# Adafruit_PowerBoost_Shield.net
KiCad netlist of a schematic drawn in EAGLE
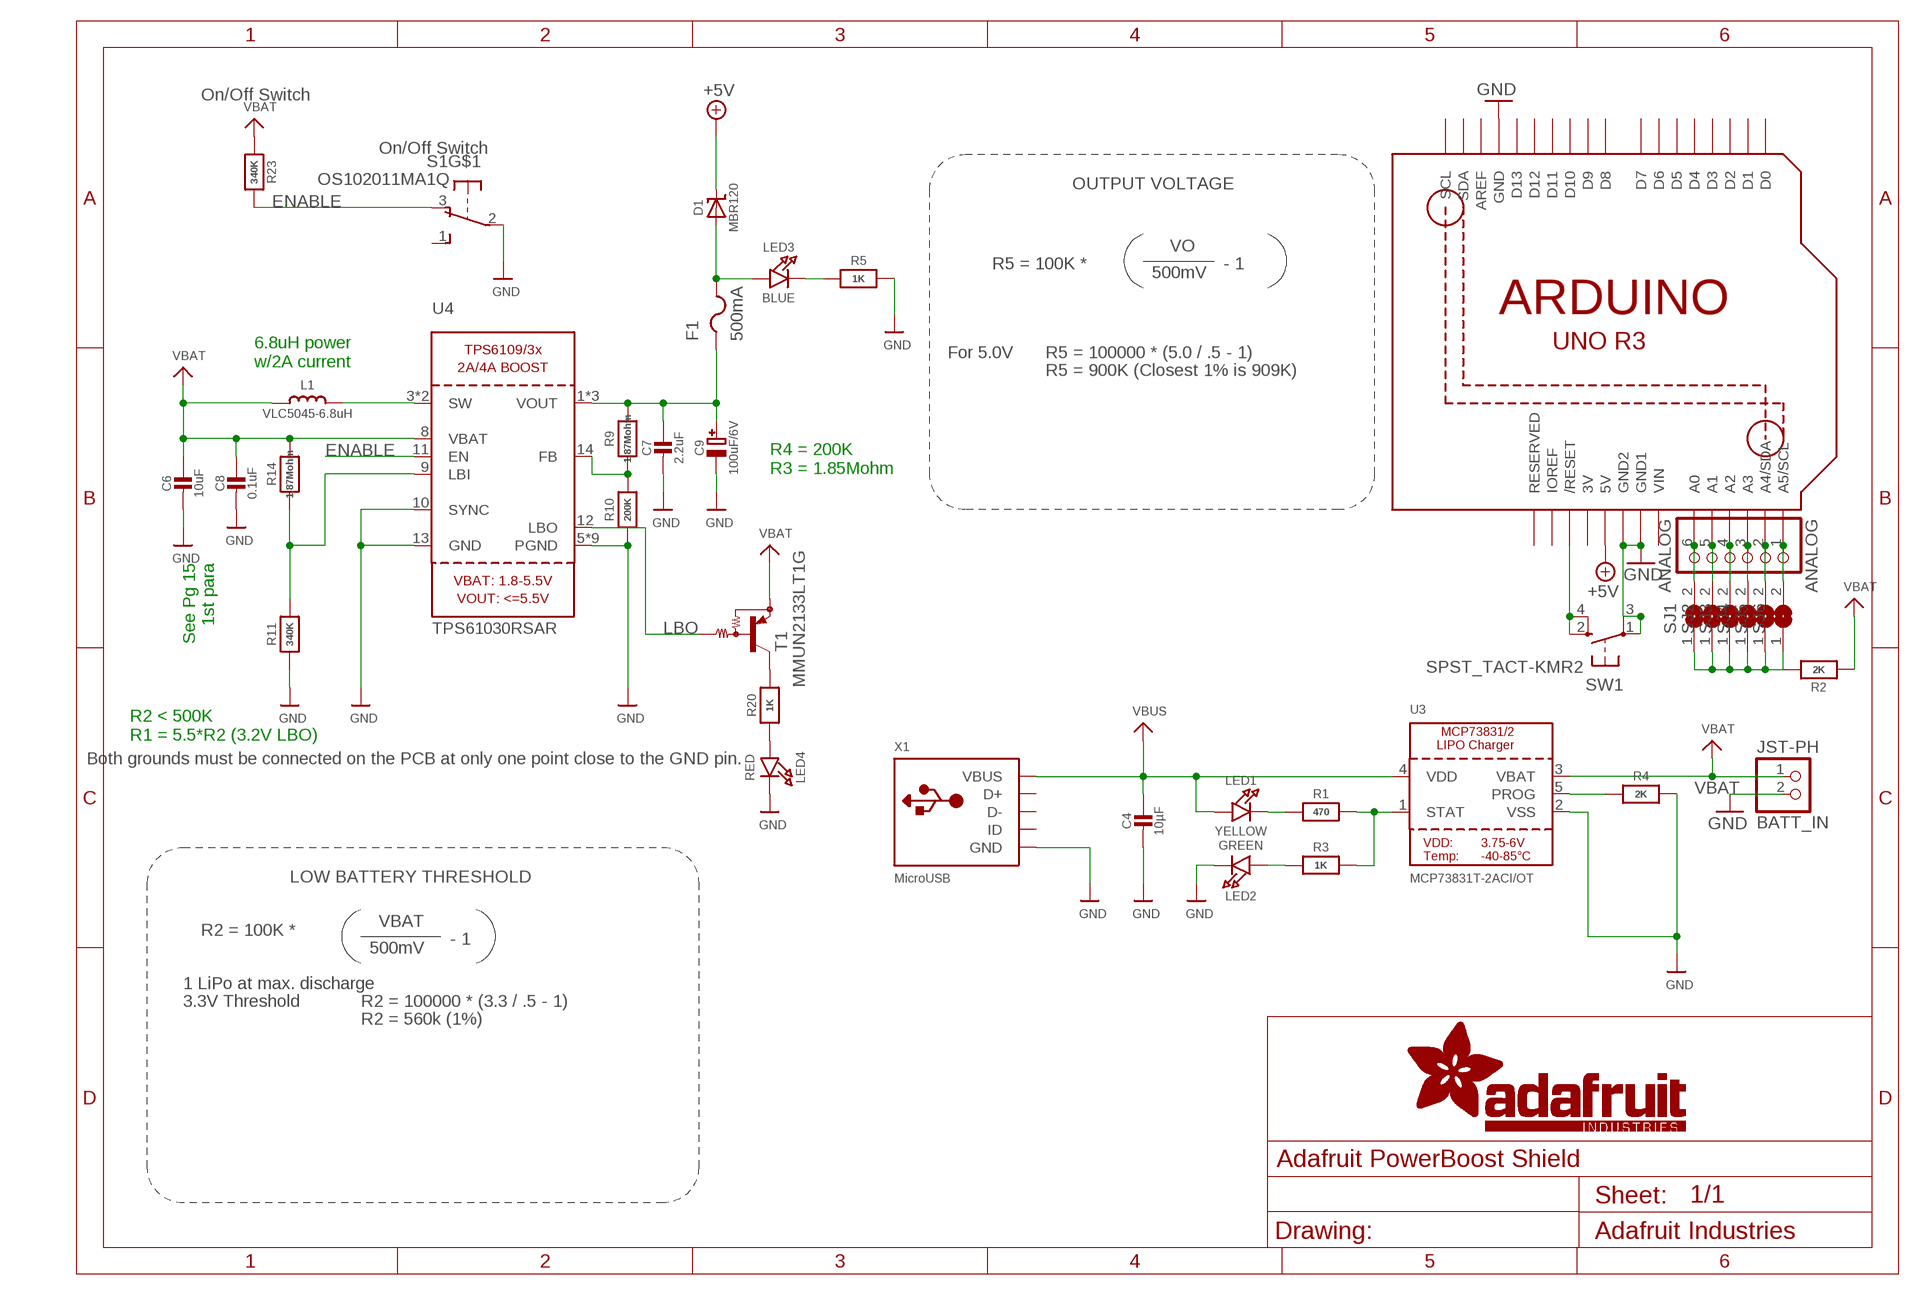
[diagram p0: schematic, sheet 1]

(export (version "E")
  (design (tool "Eeschema 10.0.6"))
  (components
    (comp (ref "ANALOG")
      (value "ANALOG")
      (footprint "eagle-import:1X06")
      (libsource (lib "eagle-import") (part "PINHD-1X6"))
    )
    (comp (ref "BATT_IN")
      (value "JST-PH")
      (footprint "eagle-import:JST-PH-2-SMT")
      (libsource (lib "eagle-import") (part "JST_2PIN-SMT"))
    )
    (comp (ref "C4")
      (value "10µF")
      (footprint "eagle-import:0805-NO")
      (libsource (lib "eagle-import") (part "CAP_CERAMIC0805-NOOUTLINE"))
    )
    (comp (ref "C6")
      (value "10uF")
      (footprint "eagle-import:0805-NO")
      (libsource (lib "eagle-import") (part "CAP_CERAMIC0805-NOOUTLINE"))
    )
    (comp (ref "C7")
      (value "2.2uF")
      (footprint "eagle-import:0805-NO")
      (libsource (lib "eagle-import") (part "CAP_CERAMIC0805-NOOUTLINE"))
    )
    (comp (ref "C8")
      (value "0.1uF")
      (footprint "eagle-import:0805-NO")
      (libsource (lib "eagle-import") (part "CAP_CERAMIC0805-NOOUTLINE"))
    )
    (comp (ref "C9")
      (value "100uF/6V")
      (footprint "eagle-import:EIA3528-21_B-R")
      (libsource (lib "eagle-import") (part "CAP_TANTALUMB/3528_REFLOW"))
    )
    (comp (ref "D1")
      (value "MBR120")
      (footprint "eagle-import:SOD-123")
      (libsource (lib "eagle-import") (part "DIODE-SCHOTTKYSOD-123"))
    )
    (comp (ref "F1")
      (value "500mA")
      (footprint "eagle-import:R1206")
      (libsource (lib "eagle-import") (part "PTCFUSE-1206"))
    )
    (comp (ref "L1")
      (value "VLC5045-6.8uH")
      (footprint "eagle-import:INDUCTOR_5X5MM_TDK_VLC5045")
      (libsource (lib "eagle-import") (part "INDUCTORTDK_VLC5045"))
    )
    (comp (ref "LED1")
      (value "YELLOW")
      (footprint "eagle-import:CHIPLED_0805_NOOUTLINE")
      (libsource (lib "eagle-import") (part "LED0805_NOOUTLINE"))
    )
    (comp (ref "LED2")
      (value "GREEN")
      (footprint "eagle-import:CHIPLED_0805_NOOUTLINE")
      (libsource (lib "eagle-import") (part "LED0805_NOOUTLINE"))
    )
    (comp (ref "LED3")
      (value "BLUE")
      (footprint "eagle-import:CHIPLED_0805_NOOUTLINE")
      (libsource (lib "eagle-import") (part "LED0805_NOOUTLINE"))
    )
    (comp (ref "LED4")
      (value "RED")
      (footprint "eagle-import:CHIPLED_0805_NOOUTLINE")
      (libsource (lib "eagle-import") (part "LED0805_NOOUTLINE"))
    )
    (comp (ref "R1")
      (value "470")
      (footprint "eagle-import:0805-NO")
      (libsource (lib "eagle-import") (part "RESISTOR0805_NOOUTLINE"))
    )
    (comp (ref "R2")
      (value "2K")
      (footprint "eagle-import:0805-NO")
      (libsource (lib "eagle-import") (part "RESISTOR0805_NOOUTLINE"))
    )
    (comp (ref "R3")
      (value "1K")
      (footprint "eagle-import:0805-NO")
      (libsource (lib "eagle-import") (part "RESISTOR0805_NOOUTLINE"))
    )
    (comp (ref "R4")
      (value "2K")
      (footprint "eagle-import:0805-NO")
      (libsource (lib "eagle-import") (part "RESISTOR0805_NOOUTLINE"))
    )
    (comp (ref "R5")
      (value "1K")
      (footprint "eagle-import:0805-NO")
      (libsource (lib "eagle-import") (part "RESISTOR0805_NOOUTLINE"))
    )
    (comp (ref "R9")
      (value "1.87Mohm")
      (footprint "eagle-import:0805-NO")
      (libsource (lib "eagle-import") (part "RESISTOR0805_NOOUTLINE"))
    )
    (comp (ref "R10")
      (value "200K")
      (footprint "eagle-import:0805-NO")
      (libsource (lib "eagle-import") (part "RESISTOR0805_NOOUTLINE"))
    )
    (comp (ref "R11")
      (value "340K")
      (footprint "eagle-import:0805-NO")
      (libsource (lib "eagle-import") (part "RESISTOR0805_NOOUTLINE"))
    )
    (comp (ref "R14")
      (value "1.87Mohm")
      (footprint "eagle-import:0805-NO")
      (libsource (lib "eagle-import") (part "RESISTOR0805_NOOUTLINE"))
    )
    (comp (ref "R20")
      (value "1K")
      (footprint "eagle-import:0805-NO")
      (libsource (lib "eagle-import") (part "RESISTOR0805_NOOUTLINE"))
    )
    (comp (ref "R23")
      (value "340K")
      (footprint "eagle-import:0805-NO")
      (libsource (lib "eagle-import") (part "RESISTOR0805_NOOUTLINE"))
    )
    (comp (ref "S1")
      (value "OS102011MA1Q")
      (footprint "eagle-import:OS102011MA1Q")
      (libsource (lib "eagle-import") (part "OS102011MA1Q"))
    )
    (comp (ref "SJ1")
      (value "SOLDERJUMPER")
      (footprint "eagle-import:SOLDERJUMPER_ARROW_NOPASTE")
      (libsource (lib "eagle-import") (part "SOLDERJUMPER"))
    )
    (comp (ref "SJ2")
      (value "SOLDERJUMPER")
      (footprint "eagle-import:SOLDERJUMPER_ARROW_NOPASTE")
      (libsource (lib "eagle-import") (part "SOLDERJUMPER"))
    )
    (comp (ref "SJ3")
      (value "SOLDERJUMPER")
      (footprint "eagle-import:SOLDERJUMPER_ARROW_NOPASTE")
      (libsource (lib "eagle-import") (part "SOLDERJUMPER"))
    )
    (comp (ref "SJ4")
      (value "SOLDERJUMPER")
      (footprint "eagle-import:SOLDERJUMPER_ARROW_NOPASTE")
      (libsource (lib "eagle-import") (part "SOLDERJUMPER"))
    )
    (comp (ref "SJ5")
      (value "SOLDERJUMPER")
      (footprint "eagle-import:SOLDERJUMPER_ARROW_NOPASTE")
      (libsource (lib "eagle-import") (part "SOLDERJUMPER"))
    )
    (comp (ref "SJ6")
      (value "SOLDERJUMPER")
      (footprint "eagle-import:SOLDERJUMPER_ARROW_NOPASTE")
      (libsource (lib "eagle-import") (part "SOLDERJUMPER"))
    )
    (comp (ref "SW1")
      (value "SPST_TACT-KMR2")
      (footprint "eagle-import:KMR2")
      (libsource (lib "eagle-import") (part "SPST_TACT-KMR2"))
    )
    (comp (ref "T1")
      (value "MMUN2133LT1G")
      (footprint "eagle-import:SC59-BEC")
      (libsource (lib "eagle-import") (part "-PNP_DRIVER-SC59-BECMUN2114T1"))
    )
    (comp (ref "U$3")
      (value "FIDUCIAL")
      (footprint "eagle-import:FIDUCIAL_1MM")
      (libsource (lib "eagle-import") (part "FIDUCIAL"))
    )
    (comp (ref "U$4")
      (value "FIDUCIAL")
      (footprint "eagle-import:FIDUCIAL_1MM")
      (libsource (lib "eagle-import") (part "FIDUCIAL"))
    )
    (comp (ref "U2")
      (value "ARDUINOR3-NOSILK")
      (footprint "eagle-import:ARDUINOR3-NOSILK")
      (libsource (lib "eagle-import") (part "ARDUINOR3-NOSILK"))
    )
    (comp (ref "U3")
      (value "MCP73831T-2ACI/OT")
      (footprint "eagle-import:SOT23-5")
      (libsource (lib "eagle-import") (part "MCP73831/2"))
    )
    (comp (ref "U4")
      (value "TPS61030RSAR")
      (footprint "eagle-import:PVQFN-16")
      (libsource (lib "eagle-import") (part "VREG_TPS6103X"))
    )
    (comp (ref "X1")
      (value "MicroUSB")
      (footprint "eagle-import:4UCONN_20329")
      (libsource (lib "eagle-import") (part "USBMICRO_20329"))
    )
  )
  (nets
    (net (code "1") (name "+5V") (class "Default")
      (node (ref "D1") (pin "C") (pinfunction "C_C") (pintype "passive"))
      (node (ref "U2") (pin "5V") (pinfunction "5V_5V") (pintype "power_in"))
    )
    (net (code "2") (name "/3V") (class "Default")
      (node (ref "U2") (pin "3V") (pinfunction "3V_3V") (pintype "power_in"))
    )
    (net (code "3") (name "/ENABLE") (class "Default")
      (node (ref "R23") (pin "2") (pinfunction "2_2") (pintype "passive"))
      (node (ref "S1") (pin "3") (pinfunction "O_3") (pintype "passive"))
      (node (ref "U4") (pin "11") (pinfunction "EN_11") (pintype "input"))
    )
    (net (code "4") (name "/LBO") (class "Default")
      (node (ref "T1") (pin "B") (pinfunction "B_B") (pintype "passive"))
      (node (ref "U4") (pin "12") (pinfunction "LBO_12") (pintype "output"))
    )
    (net (code "5") (name "/VIN") (class "Default")
      (node (ref "U2") (pin "VIN") (pinfunction "VIN_VIN") (pintype "power_in"))
    )
    (net (code "6") (name "GND") (class "Default")
      (node (ref "BATT_IN") (pin "2") (pinfunction "1_2") (pintype "passive"))
      (node (ref "C4") (pin "2") (pinfunction "2_2") (pintype "passive"))
      (node (ref "C6") (pin "2") (pinfunction "2_2") (pintype "passive"))
      (node (ref "C7") (pin "2") (pinfunction "2_2") (pintype "passive"))
      (node (ref "C8") (pin "2") (pinfunction "2_2") (pintype "passive"))
      (node (ref "C9") (pin "-") (pinfunction "-_-") (pintype "passive"))
      (node (ref "LED2") (pin "C") (pinfunction "C_C") (pintype "passive"))
      (node (ref "LED4") (pin "C") (pinfunction "C_C") (pintype "passive"))
      (node (ref "R10") (pin "1") (pinfunction "1_1") (pintype "passive"))
      (node (ref "R11") (pin "1") (pinfunction "1_1") (pintype "passive"))
      (node (ref "R4") (pin "2") (pinfunction "2_2") (pintype "passive"))
      (node (ref "R5") (pin "2") (pinfunction "2_2") (pintype "passive"))
      (node (ref "S1") (pin "2") (pinfunction "P_2") (pintype "passive"))
      (node (ref "SW1") (pin "1") (pinfunction "P_1") (pintype "passive"))
      (node (ref "SW1") (pin "3") (pinfunction "P1_3") (pintype "passive"))
      (node (ref "U2") (pin "GND") (pinfunction "GND_GND") (pintype "power_in"))
      (node (ref "U2") (pin "GND1") (pinfunction "GND1_GND1") (pintype "power_in"))
      (node (ref "U2") (pin "GND2") (pinfunction "GND2_GND2") (pintype "power_in"))
      (node (ref "U3") (pin "2") (pinfunction "VSS_2") (pintype "power_in"))
      (node (ref "U4") (pin "10") (pinfunction "SYNC_10") (pintype "input"))
      (node (ref "U4") (pin "13") (pinfunction "GND_13") (pintype "power_in"))
      (node (ref "U4") (pin "5") (pinfunction "PGND_5") (pintype "power_in"))
      (node (ref "U4") (pin "6") (pinfunction "PGND_6") (pintype "power_in"))
      (node (ref "U4") (pin "7") (pinfunction "PGND_7") (pintype "power_in"))
      (node (ref "U4") (pin "P$18") (pinfunction "PGND_P$18") (pintype "power_in"))
      (node (ref "U4") (pin "P$19") (pinfunction "PGND_P$19") (pintype "power_in"))
      (node (ref "U4") (pin "P$20") (pinfunction "PGND_P$20") (pintype "power_in"))
      (node (ref "U4") (pin "P$21") (pinfunction "PGND_P$21") (pintype "power_in"))
      (node (ref "U4") (pin "P$22") (pinfunction "PGND_P$22") (pintype "power_in"))
      (node (ref "U4") (pin "THERMAL") (pinfunction "PGND_THERMAL") (pintype "power_in"))
      (node (ref "X1") (pin "BASE@1") (pinfunction "GND_BASE@1") (pintype "power_in"))
      (node (ref "X1") (pin "BASE@2") (pinfunction "GND_BASE@2") (pintype "power_in"))
      (node (ref "X1") (pin "GND") (pinfunction "GND_GND") (pintype "power_in"))
      (node (ref "X1") (pin "SPRT@1") (pinfunction "GND_SPRT@1") (pintype "power_in"))
      (node (ref "X1") (pin "SPRT@2") (pinfunction "GND_SPRT@2") (pintype "power_in"))
      (node (ref "X1") (pin "SPRT@3") (pinfunction "GND_SPRT@3") (pintype "power_in"))
      (node (ref "X1") (pin "SPRT@4") (pinfunction "GND_SPRT@4") (pintype "power_in"))
    )
    (net (code "7") (name "Net-(ANALOG-Pad3)") (class "Default")
      (node (ref "ANALOG") (pin "3") (pinfunction "3_3") (pintype "passive"))
      (node (ref "SJ4") (pin "2") (pinfunction "2_2") (pintype "passive"))
      (node (ref "U2") (pin "A3") (pinfunction "A3_A3") (pintype "bidirectional"))
    )
    (net (code "8") (name "Net-(ANALOG-Pad4)") (class "Default")
      (node (ref "ANALOG") (pin "4") (pinfunction "4_4") (pintype "passive"))
      (node (ref "SJ3") (pin "2") (pinfunction "2_2") (pintype "passive"))
      (node (ref "U2") (pin "A2") (pinfunction "A2_A2") (pintype "bidirectional"))
    )
    (net (code "9") (name "Net-(ANALOG-Pad5)") (class "Default")
      (node (ref "ANALOG") (pin "5") (pinfunction "5_5") (pintype "passive"))
      (node (ref "SJ2") (pin "2") (pinfunction "2_2") (pintype "passive"))
      (node (ref "U2") (pin "A1") (pinfunction "A1_A1") (pintype "bidirectional"))
    )
    (net (code "10") (name "Net-(ANALOG-Pad6)") (class "Default")
      (node (ref "ANALOG") (pin "6") (pinfunction "6_6") (pintype "passive"))
      (node (ref "SJ1") (pin "2") (pinfunction "2_2") (pintype "passive"))
      (node (ref "U2") (pin "A0") (pinfunction "A0_A0") (pintype "bidirectional"))
    )
    (net (code "11") (name "Net-(C7-Pad1)") (class "Default")
      (node (ref "C7") (pin "1") (pinfunction "1_1") (pintype "passive"))
      (node (ref "C9") (pin "+") (pinfunction "+_+") (pintype "passive"))
      (node (ref "F1") (pin "1") (pinfunction "1_1") (pintype "passive"))
      (node (ref "R9") (pin "2") (pinfunction "2_2") (pintype "passive"))
      (node (ref "U4") (pin "1") (pinfunction "VOUT_1") (pintype "power_in"))
      (node (ref "U4") (pin "15") (pinfunction "VOUT_15") (pintype "power_in"))
      (node (ref "U4") (pin "16") (pinfunction "VOUT_16") (pintype "power_in"))
    )
    (net (code "12") (name "Net-(D1-PadA)") (class "Default")
      (node (ref "D1") (pin "A") (pinfunction "A_A") (pintype "passive"))
      (node (ref "F1") (pin "2") (pinfunction "2_2") (pintype "passive"))
      (node (ref "LED3") (pin "A") (pinfunction "A_A") (pintype "passive"))
    )
    (net (code "13") (name "Net-(L1-2)") (class "Default")
      (node (ref "L1") (pin "P$2") (pinfunction "2_P$2") (pintype "passive"))
      (node (ref "U4") (pin "3") (pinfunction "SW_3") (pintype "input"))
      (node (ref "U4") (pin "4") (pinfunction "SW_4") (pintype "input"))
    )
    (net (code "14") (name "Net-(LED1-PadC)") (class "Default")
      (node (ref "LED1") (pin "C") (pinfunction "C_C") (pintype "passive"))
      (node (ref "R1") (pin "1") (pinfunction "1_1") (pintype "passive"))
    )
    (net (code "15") (name "Net-(LED2-PadA)") (class "Default")
      (node (ref "LED2") (pin "A") (pinfunction "A_A") (pintype "passive"))
      (node (ref "R3") (pin "1") (pinfunction "1_1") (pintype "passive"))
    )
    (net (code "16") (name "Net-(LED3-PadC)") (class "Default")
      (node (ref "LED3") (pin "C") (pinfunction "C_C") (pintype "passive"))
      (node (ref "R5") (pin "1") (pinfunction "1_1") (pintype "passive"))
    )
    (net (code "17") (name "Net-(LED4-PadA)") (class "Default")
      (node (ref "LED4") (pin "A") (pinfunction "A_A") (pintype "passive"))
      (node (ref "R20") (pin "1") (pinfunction "1_1") (pintype "passive"))
    )
    (net (code "18") (name "Net-(R2-Pad2)") (class "Default")
      (node (ref "R2") (pin "2") (pinfunction "2_2") (pintype "passive"))
      (node (ref "SJ1") (pin "1") (pinfunction "1_1") (pintype "passive"))
      (node (ref "SJ2") (pin "1") (pinfunction "1_1") (pintype "passive"))
      (node (ref "SJ3") (pin "1") (pinfunction "1_1") (pintype "passive"))
      (node (ref "SJ4") (pin "1") (pinfunction "1_1") (pintype "passive"))
      (node (ref "SJ5") (pin "1") (pinfunction "1_1") (pintype "passive"))
      (node (ref "SJ6") (pin "1") (pinfunction "1_1") (pintype "passive"))
    )
    (net (code "19") (name "Net-(R20-Pad2)") (class "Default")
      (node (ref "R20") (pin "2") (pinfunction "2_2") (pintype "passive"))
      (node (ref "T1") (pin "C") (pinfunction "C_C") (pintype "passive"))
    )
    (net (code "20") (name "Net-(SW1-S)") (class "Default")
      (node (ref "SW1") (pin "2") (pinfunction "S_2") (pintype "passive"))
      (node (ref "SW1") (pin "4") (pinfunction "S1_4") (pintype "passive"))
      (node (ref "U2") (pin "RESET") (pinfunction "/RESET_RESET") (pintype "bidirectional"))
    )
    (net (code "21") (name "Net-(U2-A4{slash}SDA)") (class "Default")
      (node (ref "ANALOG") (pin "2") (pinfunction "2_2") (pintype "passive"))
      (node (ref "SJ5") (pin "2") (pinfunction "2_2") (pintype "passive"))
      (node (ref "U2") (pin "A4") (pinfunction "A4/SDA_A4") (pintype "bidirectional"))
    )
    (net (code "22") (name "Net-(U2-A5{slash}SCL)") (class "Default")
      (node (ref "ANALOG") (pin "1") (pinfunction "1_1") (pintype "passive"))
      (node (ref "SJ6") (pin "2") (pinfunction "2_2") (pintype "passive"))
      (node (ref "U2") (pin "A5") (pinfunction "A5/SCL_A5") (pintype "bidirectional"))
    )
    (net (code "23") (name "Net-(U3-PROG)") (class "Default")
      (node (ref "R4") (pin "1") (pinfunction "1_1") (pintype "passive"))
      (node (ref "U3") (pin "5") (pinfunction "PROG_5") (pintype "input"))
    )
    (net (code "24") (name "Net-(U3-STAT)") (class "Default")
      (node (ref "R1") (pin "2") (pinfunction "2_2") (pintype "passive"))
      (node (ref "R3") (pin "2") (pinfunction "2_2") (pintype "passive"))
      (node (ref "U3") (pin "1") (pinfunction "STAT_1") (pintype "output"))
    )
    (net (code "25") (name "Net-(U4-FB)") (class "Default")
      (node (ref "R10") (pin "2") (pinfunction "2_2") (pintype "passive"))
      (node (ref "R9") (pin "1") (pinfunction "1_1") (pintype "passive"))
      (node (ref "U4") (pin "14") (pinfunction "FB_14") (pintype "input"))
    )
    (net (code "26") (name "Net-(U4-LBI)") (class "Default")
      (node (ref "R11") (pin "2") (pinfunction "2_2") (pintype "passive"))
      (node (ref "R14") (pin "1") (pinfunction "1_1") (pintype "passive"))
      (node (ref "U4") (pin "9") (pinfunction "LBI_9") (pintype "input"))
    )
    (net (code "27") (name "VBAT") (class "Default")
      (node (ref "BATT_IN") (pin "1") (pinfunction "2_1") (pintype "passive"))
      (node (ref "C6") (pin "1") (pinfunction "1_1") (pintype "passive"))
      (node (ref "C8") (pin "1") (pinfunction "1_1") (pintype "passive"))
      (node (ref "L1") (pin "P$1") (pinfunction "1_P$1") (pintype "passive"))
      (node (ref "R14") (pin "2") (pinfunction "2_2") (pintype "passive"))
      (node (ref "R2") (pin "1") (pinfunction "1_1") (pintype "passive"))
      (node (ref "R23") (pin "1") (pinfunction "1_1") (pintype "passive"))
      (node (ref "T1") (pin "E") (pinfunction "E_E") (pintype "passive"))
      (node (ref "U3") (pin "3") (pinfunction "VBAT_3") (pintype "power_in"))
      (node (ref "U4") (pin "8") (pinfunction "VBAT_8") (pintype "input"))
    )
    (net (code "28") (name "VBUS") (class "Default")
      (node (ref "C4") (pin "1") (pinfunction "1_1") (pintype "passive"))
      (node (ref "LED1") (pin "A") (pinfunction "A_A") (pintype "passive"))
      (node (ref "U3") (pin "4") (pinfunction "VDD_4") (pintype "power_in"))
      (node (ref "X1") (pin "VBUS") (pinfunction "VBUS_VBUS") (pintype "power_in"))
    )
    (net (code "29") (name "unconnected-(S1A-S-Pad1)") (class "Default")
      (node (ref "S1") (pin "1") (pinfunction "S_1") (pintype "passive"))
    )
    (net (code "30") (name "unconnected-(U2-PadAREF)") (class "Default")
      (node (ref "U2") (pin "AREF") (pinfunction "AREF_AREF") (pintype "bidirectional"))
    )
    (net (code "31") (name "unconnected-(U2-PadD0)") (class "Default")
      (node (ref "U2") (pin "D0") (pinfunction "D0_D0") (pintype "bidirectional"))
    )
    (net (code "32") (name "unconnected-(U2-PadD1)") (class "Default")
      (node (ref "U2") (pin "D1") (pinfunction "D1_D1") (pintype "bidirectional"))
    )
    (net (code "33") (name "unconnected-(U2-PadD2)") (class "Default")
      (node (ref "U2") (pin "D2") (pinfunction "D2_D2") (pintype "bidirectional"))
    )
    (net (code "34") (name "unconnected-(U2-PadD3)") (class "Default")
      (node (ref "U2") (pin "D3") (pinfunction "D3_D3") (pintype "bidirectional"))
    )
    (net (code "35") (name "unconnected-(U2-PadD4)") (class "Default")
      (node (ref "U2") (pin "D4") (pinfunction "D4_D4") (pintype "bidirectional"))
    )
    (net (code "36") (name "unconnected-(U2-PadD5)") (class "Default")
      (node (ref "U2") (pin "D5") (pinfunction "D5_D5") (pintype "bidirectional"))
    )
    (net (code "37") (name "unconnected-(U2-PadD6)") (class "Default")
      (node (ref "U2") (pin "D6") (pinfunction "D6_D6") (pintype "bidirectional"))
    )
    (net (code "38") (name "unconnected-(U2-PadD7)") (class "Default")
      (node (ref "U2") (pin "D7") (pinfunction "D7_D7") (pintype "bidirectional"))
    )
    (net (code "39") (name "unconnected-(U2-PadD8)") (class "Default")
      (node (ref "U2") (pin "D8") (pinfunction "D8_D8") (pintype "bidirectional"))
    )
    (net (code "40") (name "unconnected-(U2-PadD9)") (class "Default")
      (node (ref "U2") (pin "D9") (pinfunction "D9_D9") (pintype "bidirectional"))
    )
    (net (code "41") (name "unconnected-(U2-PadD10)") (class "Default")
      (node (ref "U2") (pin "D10") (pinfunction "D10_D10") (pintype "bidirectional"))
    )
    (net (code "42") (name "unconnected-(U2-PadD11)") (class "Default")
      (node (ref "U2") (pin "D11") (pinfunction "D11_D11") (pintype "bidirectional"))
    )
    (net (code "43") (name "unconnected-(U2-PadD12)") (class "Default")
      (node (ref "U2") (pin "D12") (pinfunction "D12_D12") (pintype "bidirectional"))
    )
    (net (code "44") (name "unconnected-(U2-PadD13)") (class "Default")
      (node (ref "U2") (pin "D13") (pinfunction "D13_D13") (pintype "bidirectional"))
    )
    (net (code "45") (name "unconnected-(U2-PadIOREF)") (class "Default")
      (node (ref "U2") (pin "IOREF") (pinfunction "IOREF_IOREF") (pintype "output"))
    )
    (net (code "46") (name "unconnected-(U2-PadRESERVED)") (class "Default")
      (node (ref "U2") (pin "RESERVED") (pinfunction "RESERVED_RESERVED") (pintype "no_connect"))
    )
    (net (code "47") (name "unconnected-(U2-PadSCL)") (class "Default")
      (node (ref "U2") (pin "SCL") (pinfunction "SCL_SCL") (pintype "bidirectional"))
    )
    (net (code "48") (name "unconnected-(U2-PadSDA)") (class "Default")
      (node (ref "U2") (pin "SDA") (pinfunction "SDA_SDA") (pintype "bidirectional"))
    )
    (net (code "49") (name "unconnected-(X1-PadD+)") (class "Default")
      (node (ref "X1") (pin "D+") (pinfunction "D+_D+") (pintype "bidirectional"))
    )
    (net (code "50") (name "unconnected-(X1-PadD-)") (class "Default")
      (node (ref "X1") (pin "D-") (pinfunction "D-_D-") (pintype "bidirectional"))
    )
    (net (code "51") (name "unconnected-(X1-PadID)") (class "Default")
      (node (ref "X1") (pin "ID") (pinfunction "ID_ID") (pintype "bidirectional"))
    )
  )
)
